# Qunyin_mmWave_pmic.net
KiCad netlist of a schematic drawn in Altium Designer
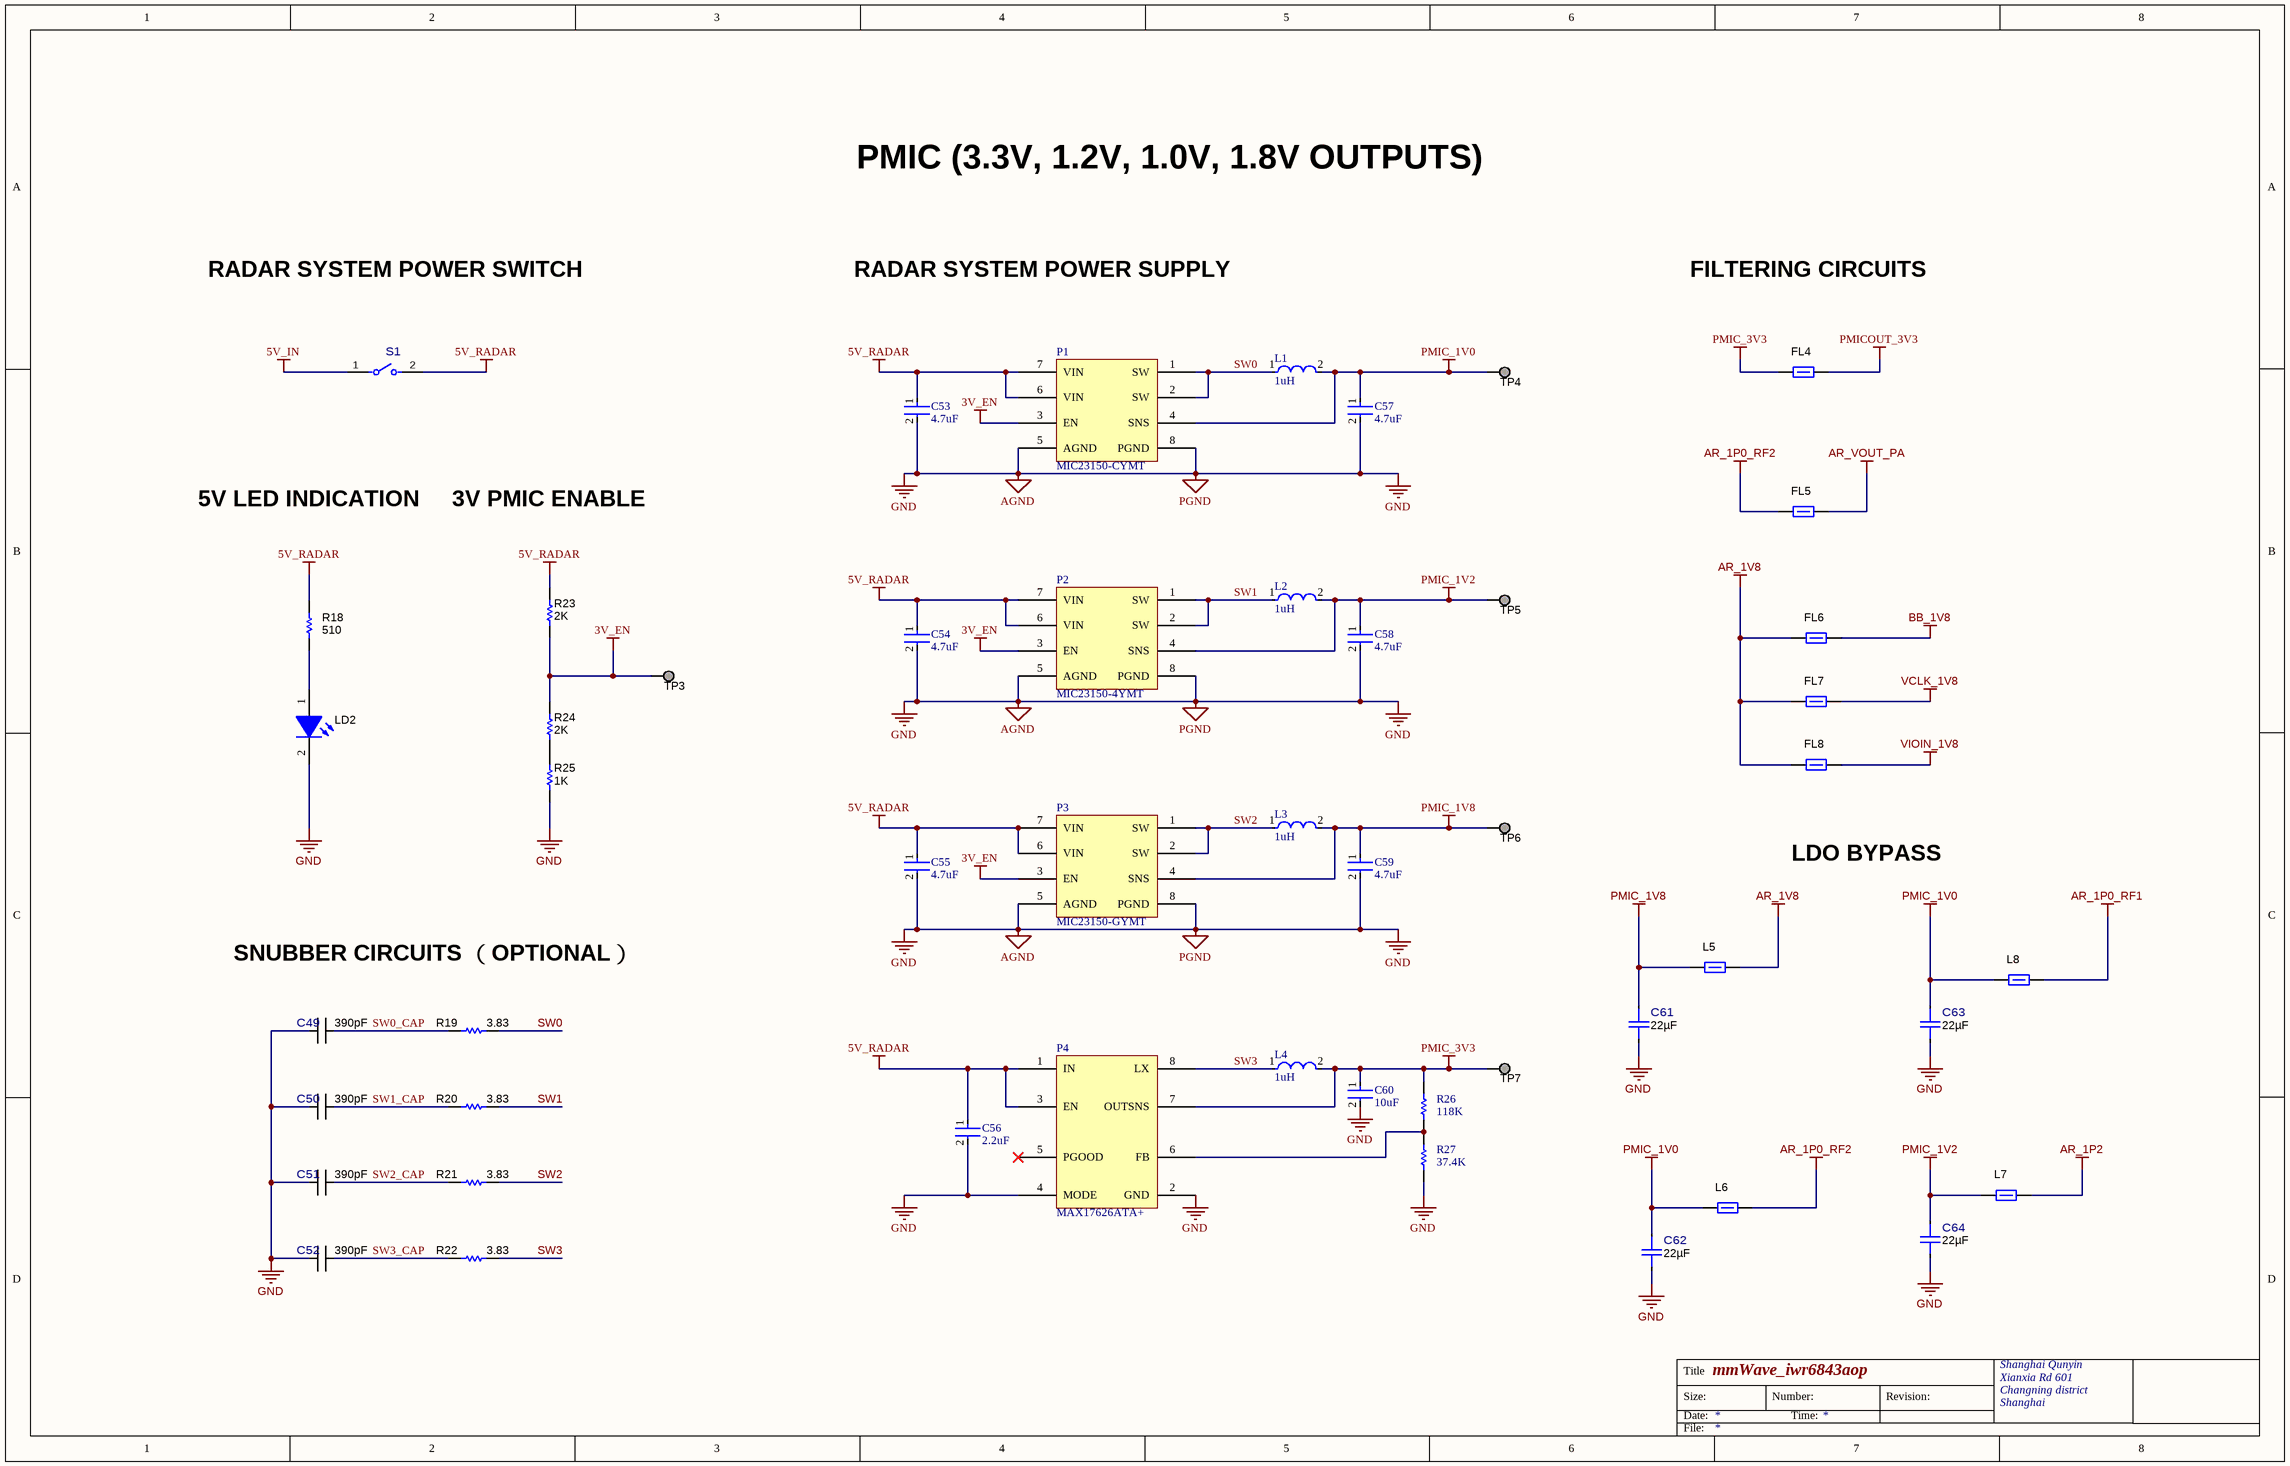
[diagram p0: Qunyin_mmWave_pmic.SchDoc]

(export (version "E")
  (design (tool "Eeschema 10.0.6"))
  (components
    (comp (ref "C49")
      (value "TMK063CG391JT-F")
      (footprint "FP-TMK063CG391JT-F_0201 (0603 Metric)-IPC_C")
      (description "CAP CER 390PF 25V C0G/NP0 0201")
      (fields (field (name "CAP_F") "390pF") (field (name "MANUFACTURER") "Taiyo Yuden"))
      (libsource (lib "Altium Vault - TI") (part "SYM-B32642B0223J"))
    )
    (comp (ref "C50")
      (value "TMK063CG391JT-F")
      (footprint "FP-TMK063CG391JT-F_0201 (0603 Metric)-IPC_C")
      (description "CAP CER 390PF 25V C0G/NP0 0201")
      (fields (field (name "CAP_F") "390pF") (field (name "MANUFACTURER") "Taiyo Yuden"))
      (libsource (lib "Altium Vault - TI") (part "SYM-B32642B0223J"))
    )
    (comp (ref "C51")
      (value "TMK063CG391JT-F")
      (footprint "FP-TMK063CG391JT-F_0201 (0603 Metric)-IPC_C")
      (description "CAP CER 390PF 25V C0G/NP0 0201")
      (fields (field (name "CAP_F") "390pF") (field (name "MANUFACTURER") "Taiyo Yuden"))
      (libsource (lib "Altium Vault - TI") (part "SYM-B32642B0223J"))
    )
    (comp (ref "C52")
      (value "TMK063CG391JT-F")
      (footprint "FP-TMK063CG391JT-F_0201 (0603 Metric)-IPC_C")
      (description "CAP CER 390PF 25V C0G/NP0 0201")
      (fields (field (name "CAP_F") "390pF") (field (name "MANUFACTURER") "Taiyo Yuden"))
      (libsource (lib "Altium Vault - TI") (part "SYM-B32642B0223J"))
    )
    (comp (ref "C53")
      (value "CL10B475KQ8NQNC")
      (footprint "FP-CL10-IPC_C")
      (description "CAP CER 4.7UF 6.3V X7R 0603")
      (fields
        (field (name "TOLERANCE") "10%")
        (field (name "CAPACITANCE") "4.7uF")
        (field (name "OCTOPART") "https://octopart.com/cl10b475kq8nqnc-samsung-24957976")
      )
      (libsource (lib "Altium Content Vault") (part "11868f565c42a9108669ba33697ecf6"))
    )
    (comp (ref "C54")
      (value "CL10B475KQ8NQNC")
      (footprint "FP-CL10-IPC_C")
      (description "CAP CER 4.7UF 6.3V X7R 0603")
      (fields
        (field (name "TOLERANCE") "10%")
        (field (name "CAPACITANCE") "4.7uF")
        (field (name "OCTOPART") "https://octopart.com/cl10b475kq8nqnc-samsung-24957976")
      )
      (libsource (lib "Altium Content Vault") (part "11868f565c42a9108669ba33697ecf6"))
    )
    (comp (ref "C55")
      (value "CL10B475KQ8NQNC")
      (footprint "FP-CL10-IPC_C")
      (description "CAP CER 4.7UF 6.3V X7R 0603")
      (fields
        (field (name "TOLERANCE") "10%")
        (field (name "CAPACITANCE") "4.7uF")
        (field (name "OCTOPART") "https://octopart.com/cl10b475kq8nqnc-samsung-24957976")
      )
      (libsource (lib "Altium Content Vault") (part "11868f565c42a9108669ba33697ecf6"))
    )
    (comp (ref "C56")
      (value "GRM188R71A225KE15D")
      (footprint "FP-GRM188-0_1-e0_2_0_5-MFG")
      (description "Chip Multilayer Ceramic Capacitors for General Purpose, 0603, 2.2uF, X7R, 15%, 10%, 10V")
      (fields
        (field (name "VOLTAGE") "10V")
        (field (name "CAPACITANCE") "2.2uF")
        (field (name "TOLERANCE") "10%")
      )
      (libsource (lib "Altium Content Vault") (part "11868f565c42a9108669ba33697ecf6"))
    )
    (comp (ref "C57")
      (value "CL10B475KQ8NQNC")
      (footprint "FP-CL10-IPC_C")
      (description "CAP CER 4.7UF 6.3V X7R 0603")
      (fields
        (field (name "TOLERANCE") "10%")
        (field (name "CAPACITANCE") "4.7uF")
        (field (name "OCTOPART") "https://octopart.com/cl10b475kq8nqnc-samsung-24957976")
      )
      (libsource (lib "Altium Content Vault") (part "11868f565c42a9108669ba33697ecf6"))
    )
    (comp (ref "C58")
      (value "CL10B475KQ8NQNC")
      (footprint "FP-CL10-IPC_C")
      (description "CAP CER 4.7UF 6.3V X7R 0603")
      (fields
        (field (name "TOLERANCE") "10%")
        (field (name "CAPACITANCE") "4.7uF")
        (field (name "OCTOPART") "https://octopart.com/cl10b475kq8nqnc-samsung-24957976")
      )
      (libsource (lib "Altium Content Vault") (part "11868f565c42a9108669ba33697ecf6"))
    )
    (comp (ref "C59")
      (value "CL10B475KQ8NQNC")
      (footprint "FP-CL10-IPC_C")
      (description "CAP CER 4.7UF 6.3V X7R 0603")
      (fields
        (field (name "TOLERANCE") "10%")
        (field (name "CAPACITANCE") "4.7uF")
        (field (name "OCTOPART") "https://octopart.com/cl10b475kq8nqnc-samsung-24957976")
      )
      (libsource (lib "Altium Content Vault") (part "11868f565c42a9108669ba33697ecf6"))
    )
    (comp (ref "C60")
      (value "GRM188Z71A106KA73D")
      (footprint "FP-GRM188-0_2-IPC_C")
      (description "Chip Multilayer Ceramic Capacitors for General Purpose, 0603, 10uF, X7R, 15%, 10%, 10V")
      (fields (field (name "CAPACITANCE") "10uF"))
      (libsource (lib "Altium Content Vault") (part "11868f565c42a9108669ba33697ecf6"))
    )
    (comp (ref "C61")
      (value "CL05A226MQ5N6J8")
      (footprint "FP-CL05A226MQ5N6J8_0402-IPC_C")
      (description "CAP CER 22UF 6.3V X5R 0402")
      (fields (field (name "CAP_F") "22µF") (field (name "MANUFACTURER") "Samsung Electro-Mechanics"))
      (libsource (lib "Altium Vault - TI") (part "SYM-C0603C220K5RACAUTO"))
    )
    (comp (ref "C62")
      (value "CL05A226MQ5N6J8")
      (footprint "FP-CL05A226MQ5N6J8_0402-IPC_C")
      (description "CAP CER 22UF 6.3V X5R 0402")
      (fields (field (name "CAP_F") "22µF") (field (name "MANUFACTURER") "Samsung Electro-Mechanics"))
      (libsource (lib "Altium Vault - TI") (part "SYM-C0603C220K5RACAUTO"))
    )
    (comp (ref "C63")
      (value "CL05A226MQ5N6J8")
      (footprint "FP-CL05A226MQ5N6J8_0402-IPC_C")
      (description "CAP CER 22UF 6.3V X5R 0402")
      (fields (field (name "CAP_F") "22µF") (field (name "MANUFACTURER") "Samsung Electro-Mechanics"))
      (libsource (lib "Altium Vault - TI") (part "SYM-C0603C220K5RACAUTO"))
    )
    (comp (ref "C64")
      (value "CL05A226MQ5N6J8")
      (footprint "FP-CL05A226MQ5N6J8_0402-IPC_C")
      (description "CAP CER 22UF 6.3V X5R 0402")
      (fields (field (name "CAP_F") "22µF") (field (name "MANUFACTURER") "Samsung Electro-Mechanics"))
      (libsource (lib "Altium Vault - TI") (part "SYM-C0603C220K5RACAUTO"))
    )
    (comp (ref "FL4")
      (value "BLM15PD300SZ1D")
      (footprint "0402L")
      (description "Inductor, Ferrite Bead, Ferrite, 2.2 A, 0.035 ohm, AEC-Q200 Grade 1, SMD")
      (fields (field (name "MANUFACTURER") "MuRata") (field (name "PUBLISHER") "Texas Instruments"))
      (libsource (lib "Altium Vault - TI") (part "Ferrite_Bead"))
    )
    (comp (ref "FL5")
      (value "BLM15PD300SZ1D")
      (footprint "0402L")
      (description "Inductor, Ferrite Bead, Ferrite, 2.2 A, 0.035 ohm, AEC-Q200 Grade 1, SMD")
      (fields (field (name "MANUFACTURER") "MuRata") (field (name "PUBLISHER") "Texas Instruments"))
      (libsource (lib "Altium Vault - TI") (part "Ferrite_Bead"))
    )
    (comp (ref "FL6")
      (value "BLM15PD300SZ1D")
      (footprint "0402L")
      (description "Inductor, Ferrite Bead, Ferrite, 2.2 A, 0.035 ohm, AEC-Q200 Grade 1, SMD")
      (fields (field (name "MANUFACTURER") "MuRata") (field (name "PUBLISHER") "Texas Instruments"))
      (libsource (lib "Altium Vault - TI") (part "Ferrite_Bead"))
    )
    (comp (ref "FL7")
      (value "BLM15PD300SZ1D")
      (footprint "0402L")
      (description "Inductor, Ferrite Bead, Ferrite, 2.2 A, 0.035 ohm, AEC-Q200 Grade 1, SMD")
      (fields (field (name "MANUFACTURER") "MuRata") (field (name "PUBLISHER") "Texas Instruments"))
      (libsource (lib "Altium Vault - TI") (part "Ferrite_Bead"))
    )
    (comp (ref "FL8")
      (value "BLM15PD300SZ1D")
      (footprint "0402L")
      (description "Inductor, Ferrite Bead, Ferrite, 2.2 A, 0.035 ohm, AEC-Q200 Grade 1, SMD")
      (fields (field (name "MANUFACTURER") "MuRata") (field (name "PUBLISHER") "Texas Instruments"))
      (libsource (lib "Altium Vault - TI") (part "Ferrite_Bead"))
    )
    (comp (ref "L1")
      (value "LQH5BPN1R0NT0L")
      (footprint "FP-LQH5BPB_T0-MFG")
      (description "Wire Wound Ferrite Inductor for Power Lines 1μH ±30% 0.0228Ω 3.1A 2020")
      (fields (field (name "TOLERANCE") "30%") (field (name "INDUCTANCE") "1uH"))
      (libsource (lib "Altium Content Vault") (part "725321dda6339637d4d059423bc1c3c"))
    )
    (comp (ref "L2")
      (value "LQH5BPN1R0NT0L")
      (footprint "FP-LQH5BPB_T0-MFG")
      (description "Wire Wound Ferrite Inductor for Power Lines 1μH ±30% 0.0228Ω 3.1A 2020")
      (fields (field (name "TOLERANCE") "30%") (field (name "INDUCTANCE") "1uH"))
      (libsource (lib "Altium Content Vault") (part "725321dda6339637d4d059423bc1c3c"))
    )
    (comp (ref "L3")
      (value "LQH5BPN1R0NT0L")
      (footprint "FP-LQH5BPB_T0-MFG")
      (description "Wire Wound Ferrite Inductor for Power Lines 1μH ±30% 0.0228Ω 3.1A 2020")
      (fields (field (name "TOLERANCE") "30%") (field (name "INDUCTANCE") "1uH"))
      (libsource (lib "Altium Content Vault") (part "725321dda6339637d4d059423bc1c3c"))
    )
    (comp (ref "L4")
      (value "LQH5BPN1R0NT0L")
      (footprint "FP-LQH5BPB_T0-MFG")
      (description "Wire Wound Ferrite Inductor for Power Lines 1μH ±30% 0.0228Ω 3.1A 2020")
      (fields (field (name "TOLERANCE") "30%") (field (name "INDUCTANCE") "1uH"))
      (libsource (lib "Altium Content Vault") (part "725321dda6339637d4d059423bc1c3c"))
    )
    (comp (ref "L5")
      (value "BLM18SG260TN1D")
      (footprint "0603L")
      (description "Ferrite Bead, 26 ohm @ 100 MHz, 6 A, 0603")
      (fields (field (name "MANUFACTURER") "MuRata") (field (name "PUBLISHER") "Texas Instruments"))
      (libsource (lib "Altium Vault - TI") (part "Ferrite_Bead"))
    )
    (comp (ref "L6")
      (value "BLM18SG260TN1D")
      (footprint "0603L")
      (description "Ferrite Bead, 26 ohm @ 100 MHz, 6 A, 0603")
      (fields (field (name "MANUFACTURER") "MuRata") (field (name "PUBLISHER") "Texas Instruments"))
      (libsource (lib "Altium Vault - TI") (part "Ferrite_Bead"))
    )
    (comp (ref "L7")
      (value "BLM18SG260TN1D")
      (footprint "0603L")
      (description "Ferrite Bead, 26 ohm @ 100 MHz, 6 A, 0603")
      (fields (field (name "MANUFACTURER") "MuRata") (field (name "PUBLISHER") "Texas Instruments"))
      (libsource (lib "Altium Vault - TI") (part "Ferrite_Bead"))
    )
    (comp (ref "L8")
      (value "BLM18SG260TN1D")
      (footprint "0603L")
      (description "Ferrite Bead, 26 ohm @ 100 MHz, 6 A, 0603")
      (fields (field (name "MANUFACTURER") "MuRata") (field (name "PUBLISHER") "Texas Instruments"))
      (libsource (lib "Altium Vault - TI") (part "Ferrite_Bead"))
    )
    (comp (ref "LD2")
      (value "APHHS1005CGCK")
      (footprint "APHHS1005_Green")
      (description "LED, Green, SMD")
      (fields (field (name "MANUFACTURER") "Kingbright"))
      (libsource (lib "Altium Vault - TI") (part "LED"))
    )
    (comp (ref "P1")
      (value "MIC23150-CYMT")
      (description "pmic 1V 2A 4MHz")
      (libsource (lib "MIC23150-CYMT") (part "MIC23150-CYMT"))
    )
    (comp (ref "P2")
      (value "MIC23150-4YMT")
      (description "pmic 1.2V 2A 4MHz")
      (libsource (lib "MIC23150-4YMT") (part "MIC23150-4YMT"))
    )
    (comp (ref "P3")
      (value "MIC23150-GYMT")
      (description "pmic 1.8V 2A 4MHz")
      (libsource (lib "MIC23150-GYMT") (part "MIC23150-GYMT"))
    )
    (comp (ref "P4")
      (value "MAX17626ATA+")
      (description "IC 3.3V Adj Out Dc-dc Tdfn")
      (fields (field (name "MANUFACTURER") "Analog Devices"))
      (libsource (lib "MAX17626") (part "MAX17626"))
    )
    (comp (ref "R18")
      (value "510")
      (footprint "0201L")
      (description "RES, 510, 5%, 0.05 W, 0201")
      (fields
        (field (name "MANUFACTURER") "Yageo America")
        (field (name "PARTNUMBER") "RC0201JR-07510RL")
        (field (name "PUBLISHER") "Texas Instruments")
      )
      (libsource (lib "Altium Vault - TI") (part "Resistor"))
    )
    (comp (ref "R19")
      (value "RC0402FR-073R83L")
      (footprint "FP-RC0402FR-073R83L_0402 (1005 Metric)-IPC_C")
      (description "RES Thick Film SMD 3.83Ω 1% 1/16W 0402 200ppm/°C")
      (fields (field (name "RES_OHM") "3.83") (field (name "MANUFACTURER") "Yageo"))
      (libsource (lib "Altium Vault - TI") (part "SYM-WSR3R1500F"))
    )
    (comp (ref "R20")
      (value "RC0402FR-073R83L")
      (footprint "FP-RC0402FR-073R83L_0402 (1005 Metric)-IPC_C")
      (description "RES Thick Film SMD 3.83Ω 1% 1/16W 0402 200ppm/°C")
      (fields (field (name "RES_OHM") "3.83") (field (name "MANUFACTURER") "Yageo"))
      (libsource (lib "Altium Vault - TI") (part "SYM-WSR3R1500F"))
    )
    (comp (ref "R21")
      (value "RC0402FR-073R83L")
      (footprint "FP-RC0402FR-073R83L_0402 (1005 Metric)-IPC_C")
      (description "RES Thick Film SMD 3.83Ω 1% 1/16W 0402 200ppm/°C")
      (fields (field (name "RES_OHM") "3.83") (field (name "MANUFACTURER") "Yageo"))
      (libsource (lib "Altium Vault - TI") (part "SYM-WSR3R1500F"))
    )
    (comp (ref "R22")
      (value "RC0402FR-073R83L")
      (footprint "FP-RC0402FR-073R83L_0402 (1005 Metric)-IPC_C")
      (description "RES Thick Film SMD 3.83Ω 1% 1/16W 0402 200ppm/°C")
      (fields (field (name "RES_OHM") "3.83") (field (name "MANUFACTURER") "Yageo"))
      (libsource (lib "Altium Vault - TI") (part "SYM-WSR3R1500F"))
    )
    (comp (ref "R23")
      (value "2K")
      (footprint "FP-RMCF0603-IPC_A")
      (description "Res Thick Film 0603 2K Ohm 1% 0.1W(1/10W) ±100ppm/C Pad SMD Automotive T/R")
      (fields
        (field (name "MANUFACTURER") "Stackpole Electronics")
        (field (name "MANUFACTURER PART NUMBER") "RMCF0603FT2K00")
      )
      (libsource (lib "Simulation Generic Components") (part "Resistor"))
    )
    (comp (ref "R24")
      (value "2K")
      (footprint "FP-RMCF0603-IPC_A")
      (description "Res Thick Film 0603 2K Ohm 1% 0.1W(1/10W) ±100ppm/C Pad SMD Automotive T/R")
      (fields
        (field (name "MANUFACTURER") "Stackpole Electronics")
        (field (name "MANUFACTURER PART NUMBER") "RMCF0603FT2K00")
      )
      (libsource (lib "Simulation Generic Components") (part "Resistor"))
    )
    (comp (ref "R25")
      (value "1K")
      (footprint "FP-RMCF0603-IPC_A")
      (description "Res Thick Film 0201 1K Ohm 5% 0.05W(1/20W) ±250ppm/C Pad SMD T/R")
      (fields
        (field (name "MANUFACTURER") "Samsung")
        (field (name "MANUFACTURER PART NUMBER") "RC0603J102CS")
      )
      (libsource (lib "Simulation Generic Components") (part "Resistor"))
    )
    (comp (ref "R26")
      (value "118K")
      (footprint "FP-CRCW1206-e3-IPC_A")
      (description "Res Thick Film 1206 118K Ohm 1% 1/4W ±100ppm/°C Molded SMD SMD Paper T/R")
      (fields
        (field (name "MANUFACTURER") "Vishay")
        (field (name "MANUFACTURER PART NUMBER") "CRCW1206118KFKEA")
      )
      (libsource (lib "Simulation Generic Components") (part "Resistor"))
    )
    (comp (ref "R27")
      (value "37.4K")
      (footprint "FP-CRCW1206-e3-IPC_A")
      (description "Res Thick Film 1206 37.4K Ohm 1% 1/4W ±100ppm/°C Molded SMD Punched Carrier T/R")
      (fields
        (field (name "MANUFACTURER") "Panasonic")
        (field (name "MANUFACTURER PART NUMBER") "ERJ-8ENF3742V")
      )
      (libsource (lib "Simulation Generic Components") (part "Resistor"))
    )
    (comp (ref "S1")
      (value "CHS-01TA")
      (footprint "FP-CHS-01TA_SMT_SW_5MM4_2MM5-MFG")
      (description "SWITCH SLIDE DIP SPST 100MA 6V")
      (fields (field (name "MANUFACTURER") "Nidec Copal Electronics"))
      (libsource (lib "Altium Vault - TI") (part "SYM-PTS635SK25SM"))
    )
    (comp (ref "TP3")
      (value "TESTPOINT")
      (footprint "TP_25MIL-SMT")
      (description "TEST POINT.  No entry in BOM.")
      (libsource (lib "Altium Vault - TI") (part "TESTPOINT"))
    )
    (comp (ref "TP4")
      (value "TESTPOINT")
      (footprint "TP_25MIL-SMT")
      (description "TEST POINT.  No entry in BOM.")
      (libsource (lib "Altium Vault - TI") (part "TESTPOINT"))
    )
    (comp (ref "TP5")
      (value "TESTPOINT")
      (footprint "TP_25MIL-SMT")
      (description "TEST POINT.  No entry in BOM.")
      (libsource (lib "Altium Vault - TI") (part "TESTPOINT"))
    )
    (comp (ref "TP6")
      (value "TESTPOINT")
      (footprint "TP_25MIL-SMT")
      (description "TEST POINT.  No entry in BOM.")
      (libsource (lib "Altium Vault - TI") (part "TESTPOINT"))
    )
    (comp (ref "TP7")
      (value "TESTPOINT")
      (footprint "TP_25MIL-SMT")
      (description "TEST POINT.  No entry in BOM.")
      (libsource (lib "Altium Vault - TI") (part "TESTPOINT"))
    )
  )
  (nets
    (net (code "1") (name "/SW0") (class "Default")
      (node (ref "L1") (pin "1") (pinfunction "1_1") (pintype "passive"))
      (node (ref "P1") (pin "1") (pinfunction "SW_1") (pintype "passive"))
      (node (ref "P1") (pin "2") (pinfunction "SW_2") (pintype "passive"))
      (node (ref "R19") (pin "2") (pinfunction "2_2") (pintype "passive"))
    )
    (net (code "2") (name "/SW0_CAP") (class "Default")
      (node (ref "C49") (pin "1") (pinfunction "1_1") (pintype "passive"))
      (node (ref "R19") (pin "1") (pinfunction "1_1") (pintype "passive"))
    )
    (net (code "3") (name "/SW1") (class "Default")
      (node (ref "L2") (pin "1") (pinfunction "1_1") (pintype "passive"))
      (node (ref "P2") (pin "1") (pinfunction "SW_1") (pintype "passive"))
      (node (ref "P2") (pin "2") (pinfunction "SW_2") (pintype "passive"))
      (node (ref "R20") (pin "2") (pinfunction "2_2") (pintype "passive"))
    )
    (net (code "4") (name "/SW1_CAP") (class "Default")
      (node (ref "C50") (pin "1") (pinfunction "1_1") (pintype "passive"))
      (node (ref "R20") (pin "1") (pinfunction "1_1") (pintype "passive"))
    )
    (net (code "5") (name "/SW2") (class "Default")
      (node (ref "L3") (pin "1") (pinfunction "1_1") (pintype "passive"))
      (node (ref "P3") (pin "1") (pinfunction "SW_1") (pintype "passive"))
      (node (ref "P3") (pin "2") (pinfunction "SW_2") (pintype "passive"))
      (node (ref "R21") (pin "2") (pinfunction "2_2") (pintype "passive"))
    )
    (net (code "6") (name "/SW2_CAP") (class "Default")
      (node (ref "C51") (pin "1") (pinfunction "1_1") (pintype "passive"))
      (node (ref "R21") (pin "1") (pinfunction "1_1") (pintype "passive"))
    )
    (net (code "7") (name "/SW3") (class "Default")
      (node (ref "L4") (pin "1") (pinfunction "1_1") (pintype "passive"))
      (node (ref "P4") (pin "8") (pinfunction "LX_8") (pintype "passive"))
      (node (ref "R22") (pin "2") (pinfunction "2_2") (pintype "passive"))
    )
    (net (code "8") (name "/SW3_CAP") (class "Default")
      (node (ref "C52") (pin "1") (pinfunction "1_1") (pintype "passive"))
      (node (ref "R22") (pin "1") (pinfunction "1_1") (pintype "passive"))
    )
    (net (code "9") (name "3V_EN") (class "Default")
      (node (ref "P1") (pin "3") (pinfunction "EN_3") (pintype "tri_state"))
      (node (ref "P2") (pin "3") (pinfunction "EN_3") (pintype "tri_state"))
      (node (ref "P3") (pin "3") (pinfunction "EN_3") (pintype "tri_state"))
      (node (ref "R23") (pin "1") (pinfunction "1_1") (pintype "passive"))
      (node (ref "R24") (pin "2") (pinfunction "2_2") (pintype "passive"))
      (node (ref "TP3") (pin "1") (pintype "passive"))
    )
    (net (code "10") (name "5V_IN") (class "Default")
      (node (ref "S1") (pin "1") (pinfunction "1_1") (pintype "passive"))
    )
    (net (code "11") (name "5V_RADAR") (class "Default")
      (node (ref "C53") (pin "1") (pinfunction "1_1") (pintype "passive"))
      (node (ref "C54") (pin "1") (pinfunction "1_1") (pintype "passive"))
      (node (ref "C55") (pin "1") (pinfunction "1_1") (pintype "passive"))
      (node (ref "C56") (pin "1") (pinfunction "1_1") (pintype "passive"))
      (node (ref "P1") (pin "6") (pinfunction "VIN_6") (pintype "power_in"))
      (node (ref "P1") (pin "7") (pinfunction "VIN_7") (pintype "power_in"))
      (node (ref "P2") (pin "6") (pinfunction "VIN_6") (pintype "power_in"))
      (node (ref "P2") (pin "7") (pinfunction "VIN_7") (pintype "power_in"))
      (node (ref "P3") (pin "6") (pinfunction "VIN_6") (pintype "power_in"))
      (node (ref "P3") (pin "7") (pinfunction "VIN_7") (pintype "power_in"))
      (node (ref "P4") (pin "1") (pinfunction "IN_1") (pintype "power_in"))
      (node (ref "P4") (pin "3") (pinfunction "EN_3") (pintype "passive"))
      (node (ref "R18") (pin "1") (pinfunction "1_1") (pintype "passive"))
      (node (ref "R23") (pin "2") (pinfunction "2_2") (pintype "passive"))
      (node (ref "S1") (pin "2") (pinfunction "2_2") (pintype "passive"))
    )
    (net (code "12") (name "AGND") (class "Default")
      (node (ref "C49") (pin "2") (pinfunction "2_2") (pintype "passive"))
      (node (ref "C50") (pin "2") (pinfunction "2_2") (pintype "passive"))
      (node (ref "C51") (pin "2") (pinfunction "2_2") (pintype "passive"))
      (node (ref "C52") (pin "2") (pinfunction "2_2") (pintype "passive"))
      (node (ref "C53") (pin "2") (pinfunction "2_2") (pintype "passive"))
      (node (ref "C54") (pin "2") (pinfunction "2_2") (pintype "passive"))
      (node (ref "C55") (pin "2") (pinfunction "2_2") (pintype "passive"))
      (node (ref "C56") (pin "2") (pinfunction "2_2") (pintype "passive"))
      (node (ref "C57") (pin "2") (pinfunction "2_2") (pintype "passive"))
      (node (ref "C58") (pin "2") (pinfunction "2_2") (pintype "passive"))
      (node (ref "C59") (pin "2") (pinfunction "2_2") (pintype "passive"))
      (node (ref "C60") (pin "2") (pinfunction "2_2") (pintype "passive"))
      (node (ref "C61") (pin "2") (pinfunction "2_2") (pintype "passive"))
      (node (ref "C62") (pin "2") (pinfunction "2_2") (pintype "passive"))
      (node (ref "C63") (pin "2") (pinfunction "2_2") (pintype "passive"))
      (node (ref "C64") (pin "2") (pinfunction "2_2") (pintype "passive"))
      (node (ref "LD2") (pin "2") (pinfunction "K_2") (pintype "passive"))
      (node (ref "P1") (pin "5") (pinfunction "AGND_5") (pintype "passive"))
      (node (ref "P1") (pin "8") (pinfunction "PGND_8") (pintype "passive"))
      (node (ref "P2") (pin "5") (pinfunction "AGND_5") (pintype "passive"))
      (node (ref "P2") (pin "8") (pinfunction "PGND_8") (pintype "passive"))
      (node (ref "P3") (pin "5") (pinfunction "AGND_5") (pintype "passive"))
      (node (ref "P3") (pin "8") (pinfunction "PGND_8") (pintype "passive"))
      (node (ref "P4") (pin "2") (pinfunction "GND_2") (pintype "passive"))
      (node (ref "P4") (pin "4") (pinfunction "MODE_4") (pintype "passive"))
      (node (ref "R25") (pin "1") (pinfunction "1_1") (pintype "passive"))
      (node (ref "R27") (pin "1") (pinfunction "1_1") (pintype "passive"))
    )
    (net (code "13") (name "AR_1P0_RF1") (class "Default")
      (node (ref "L8") (pin "2") (pinfunction "2_2") (pintype "passive"))
    )
    (net (code "14") (name "AR_1P0_RF2") (class "Default")
      (node (ref "FL5") (pin "1") (pinfunction "1_1") (pintype "passive"))
      (node (ref "L6") (pin "2") (pinfunction "2_2") (pintype "passive"))
    )
    (net (code "15") (name "AR_1P2") (class "Default")
      (node (ref "L7") (pin "2") (pinfunction "2_2") (pintype "passive"))
    )
    (net (code "16") (name "AR_1V8") (class "Default")
      (node (ref "FL6") (pin "1") (pinfunction "1_1") (pintype "passive"))
      (node (ref "FL7") (pin "1") (pinfunction "1_1") (pintype "passive"))
      (node (ref "FL8") (pin "1") (pinfunction "1_1") (pintype "passive"))
      (node (ref "L5") (pin "2") (pinfunction "2_2") (pintype "passive"))
    )
    (net (code "17") (name "AR_VOUT_PA") (class "Default")
      (node (ref "FL5") (pin "2") (pinfunction "2_2") (pintype "passive"))
    )
    (net (code "18") (name "BB_1V8") (class "Default")
      (node (ref "FL6") (pin "2") (pinfunction "2_2") (pintype "passive"))
    )
    (net (code "19") (name "Net-(LD2-A)") (class "Default")
      (node (ref "LD2") (pin "1") (pinfunction "A_1") (pintype "passive"))
      (node (ref "R18") (pin "2") (pinfunction "2_2") (pintype "passive"))
    )
    (net (code "20") (name "Net-(P4-FB)") (class "Default")
      (node (ref "P4") (pin "6") (pinfunction "FB_6") (pintype "tri_state"))
      (node (ref "R26") (pin "1") (pinfunction "1_1") (pintype "passive"))
      (node (ref "R27") (pin "2") (pinfunction "2_2") (pintype "passive"))
    )
    (net (code "21") (name "Net-(R24-Pad1)") (class "Default")
      (node (ref "R24") (pin "1") (pinfunction "1_1") (pintype "passive"))
      (node (ref "R25") (pin "2") (pinfunction "2_2") (pintype "passive"))
    )
    (net (code "22") (name "PMICOUT_3V3") (class "Default")
      (node (ref "FL4") (pin "2") (pinfunction "2_2") (pintype "passive"))
    )
    (net (code "23") (name "PMIC_1V0") (class "Default")
      (node (ref "C57") (pin "1") (pinfunction "1_1") (pintype "passive"))
      (node (ref "C62") (pin "1") (pinfunction "1_1") (pintype "passive"))
      (node (ref "C63") (pin "1") (pinfunction "1_1") (pintype "passive"))
      (node (ref "L1") (pin "2") (pinfunction "2_2") (pintype "passive"))
      (node (ref "L6") (pin "1") (pinfunction "1_1") (pintype "passive"))
      (node (ref "L8") (pin "1") (pinfunction "1_1") (pintype "passive"))
      (node (ref "P1") (pin "4") (pinfunction "SNS_4") (pintype "passive"))
      (node (ref "TP4") (pin "1") (pintype "passive"))
    )
    (net (code "24") (name "PMIC_1V2") (class "Default")
      (node (ref "C58") (pin "1") (pinfunction "1_1") (pintype "passive"))
      (node (ref "C64") (pin "1") (pinfunction "1_1") (pintype "passive"))
      (node (ref "L2") (pin "2") (pinfunction "2_2") (pintype "passive"))
      (node (ref "L7") (pin "1") (pinfunction "1_1") (pintype "passive"))
      (node (ref "P2") (pin "4") (pinfunction "SNS_4") (pintype "passive"))
      (node (ref "TP5") (pin "1") (pintype "passive"))
    )
    (net (code "25") (name "PMIC_1V8") (class "Default")
      (node (ref "C59") (pin "1") (pinfunction "1_1") (pintype "passive"))
      (node (ref "C61") (pin "1") (pinfunction "1_1") (pintype "passive"))
      (node (ref "L3") (pin "2") (pinfunction "2_2") (pintype "passive"))
      (node (ref "L5") (pin "1") (pinfunction "1_1") (pintype "passive"))
      (node (ref "P3") (pin "4") (pinfunction "SNS_4") (pintype "passive"))
      (node (ref "TP6") (pin "1") (pintype "passive"))
    )
    (net (code "26") (name "PMIC_3V3") (class "Default")
      (node (ref "C60") (pin "1") (pinfunction "1_1") (pintype "passive"))
      (node (ref "FL4") (pin "1") (pinfunction "1_1") (pintype "passive"))
      (node (ref "L4") (pin "2") (pinfunction "2_2") (pintype "passive"))
      (node (ref "P4") (pin "7") (pinfunction "OUTSNS_7") (pintype "passive"))
      (node (ref "R26") (pin "2") (pinfunction "2_2") (pintype "passive"))
      (node (ref "TP7") (pin "1") (pintype "passive"))
    )
    (net (code "27") (name "VCLK_1V8") (class "Default")
      (node (ref "FL7") (pin "2") (pinfunction "2_2") (pintype "passive"))
    )
    (net (code "28") (name "VIOIN_1V8") (class "Default")
      (node (ref "FL8") (pin "2") (pinfunction "2_2") (pintype "passive"))
    )
    (net (code "29") (name "unconnected-(P4-PGOOD-Pad5)") (class "Default")
      (node (ref "P4") (pin "5") (pinfunction "PGOOD_5") (pintype "passive+no_connect"))
    )
  )
)
